# MonoPedal.net
KiCad netlist of a schematic drawn in EAGLE
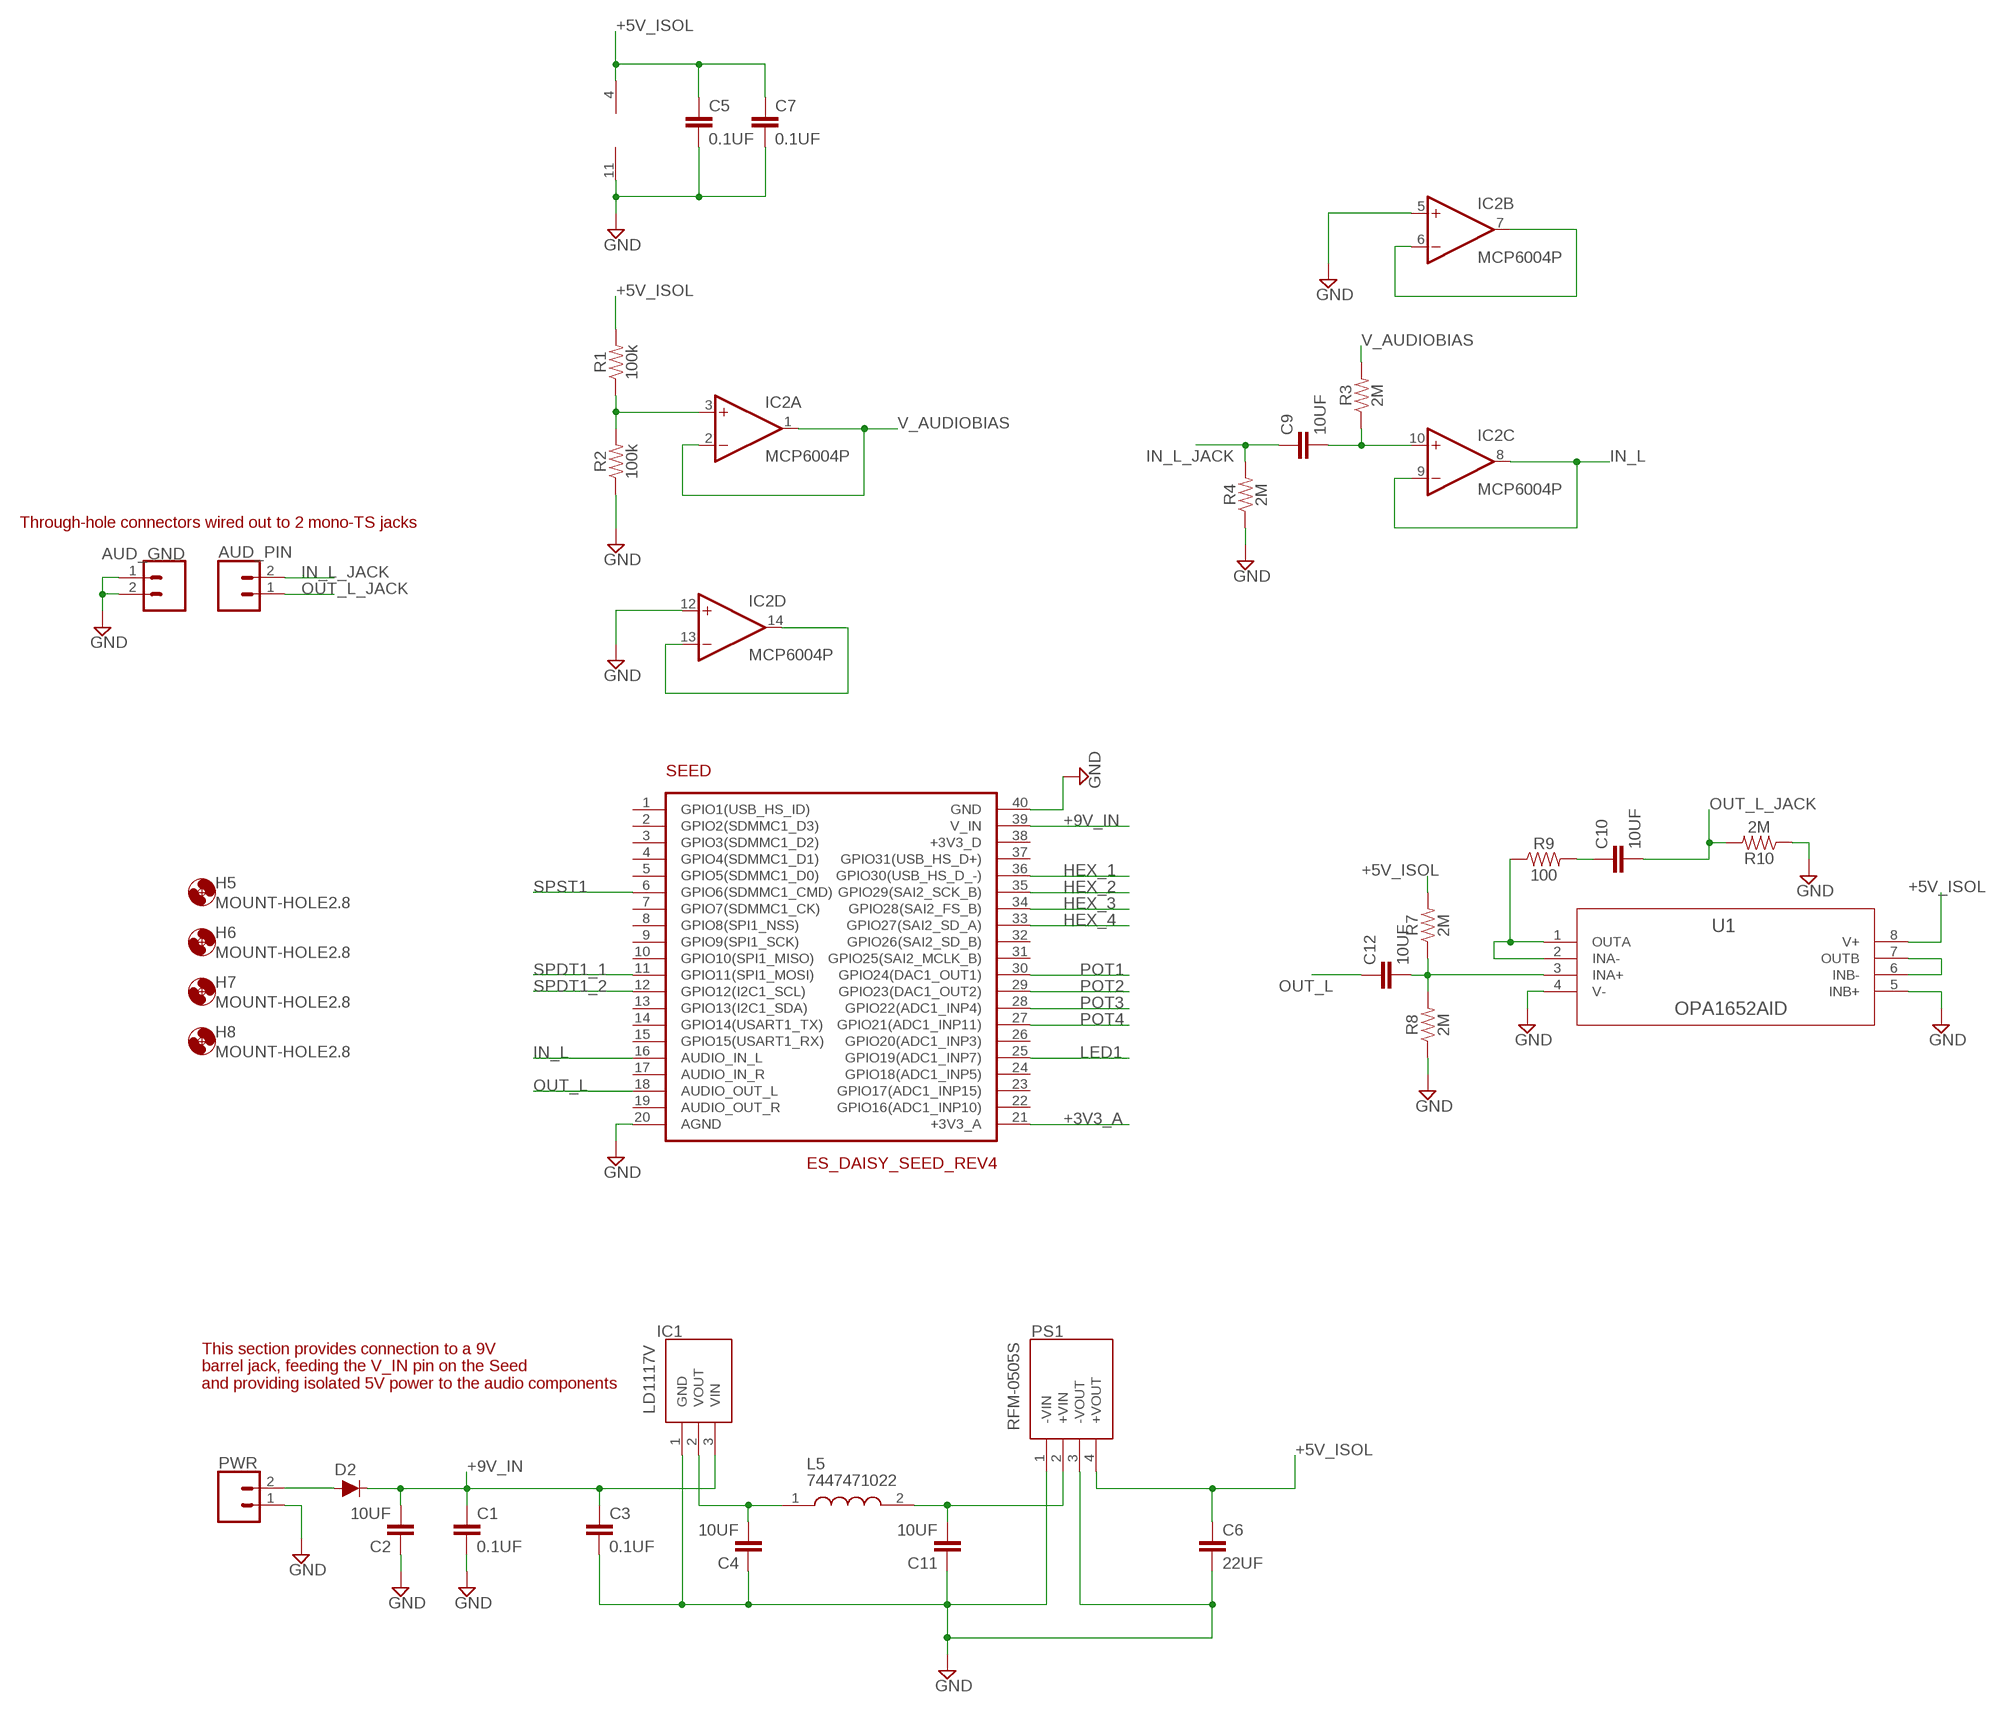
[diagram p0: schematic, sheet 1]
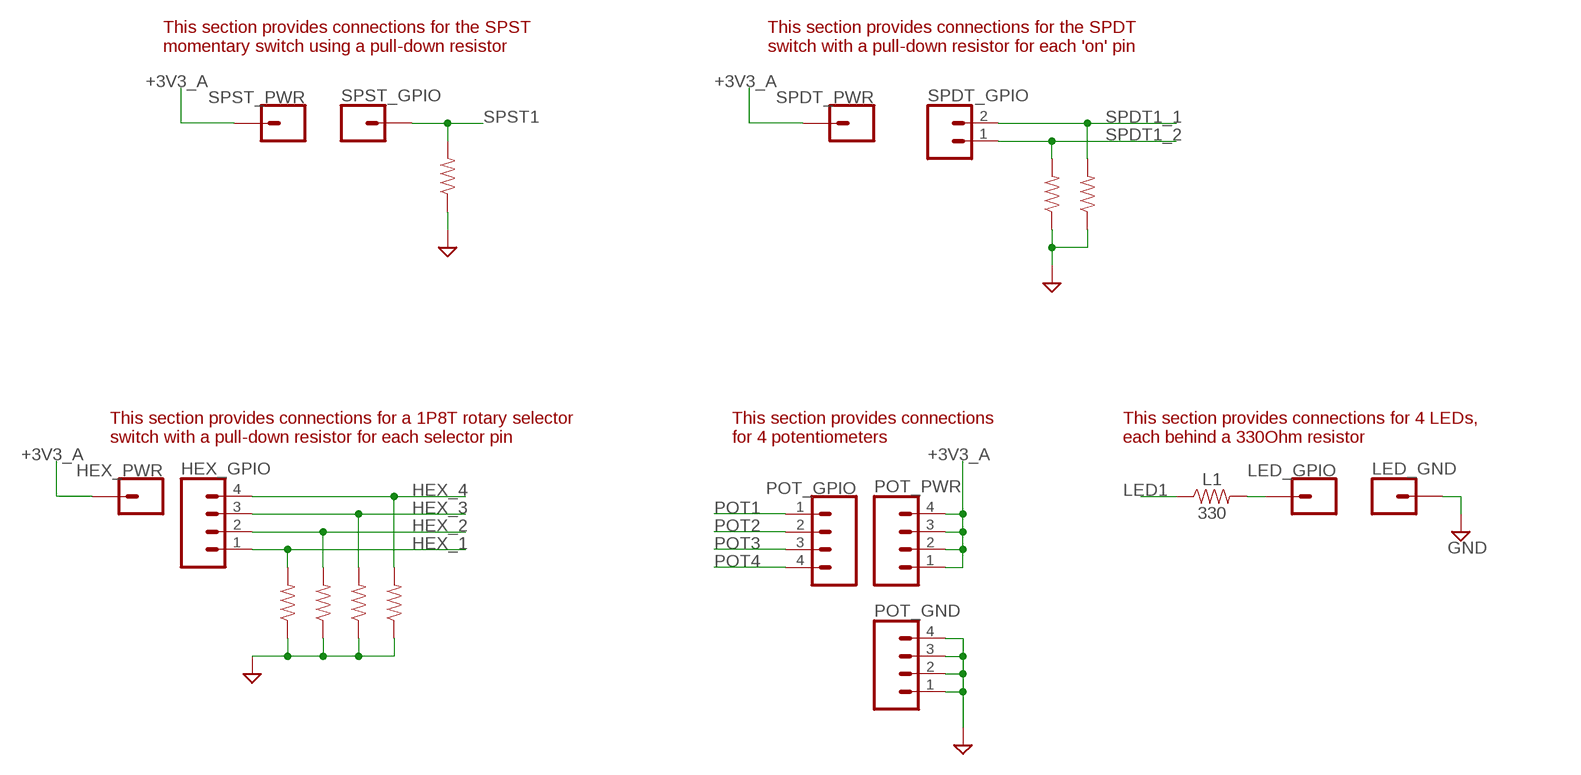
[diagram p1: schematic, sheet 2]

(export (version "E")
  (design (tool "Eeschema 10.0.6"))
  (components
    (comp (ref "AUD_GND")
      (value "CONN_02")
      (footprint "eagle-import:1X02")
      (libsource (lib "eagle-import") (part "CONN_02"))
    )
    (comp (ref "AUD_PIN")
      (value "CONN_02")
      (footprint "eagle-import:1X02")
      (libsource (lib "eagle-import") (part "CONN_02"))
    )
    (comp (ref "C1")
      (value "0.1UF")
      (footprint "eagle-import:CAP-PTH-SMALL-KIT")
      (libsource (lib "eagle-import") (part "0.1UF"))
    )
    (comp (ref "C2")
      (value "10UF")
      (footprint "eagle-import:CAP-PTH-SMALL-KIT")
      (libsource (lib "eagle-import") (part "10UF"))
    )
    (comp (ref "C3")
      (value "0.1UF")
      (footprint "eagle-import:CAP-PTH-SMALL-KIT")
      (libsource (lib "eagle-import") (part "0.1UF"))
    )
    (comp (ref "C4")
      (value "10UF")
      (footprint "eagle-import:CAP-PTH-SMALL-KIT")
      (libsource (lib "eagle-import") (part "10UF"))
    )
    (comp (ref "C5")
      (value "0.1UF")
      (footprint "eagle-import:CAP-PTH-SMALL-KIT")
      (libsource (lib "eagle-import") (part "0.1UF"))
    )
    (comp (ref "C6")
      (value "22UF")
      (footprint "eagle-import:CAP-PTH-SMALL-KIT")
      (libsource (lib "eagle-import") (part "22UF"))
    )
    (comp (ref "C7")
      (value "0.1UF")
      (footprint "eagle-import:CAP-PTH-SMALL-KIT")
      (libsource (lib "eagle-import") (part "0.1UF"))
    )
    (comp (ref "C9")
      (value "10UF")
      (footprint "eagle-import:CAP-PTH-SMALL-KIT")
      (libsource (lib "eagle-import") (part "10UF"))
    )
    (comp (ref "C10")
      (value "10UF")
      (footprint "eagle-import:CAP-PTH-SMALL-KIT")
      (libsource (lib "eagle-import") (part "10UF"))
    )
    (comp (ref "C11")
      (value "10UF")
      (footprint "eagle-import:CAP-PTH-SMALL-KIT")
      (libsource (lib "eagle-import") (part "10UF"))
    )
    (comp (ref "C12")
      (value "10UF")
      (footprint "eagle-import:CAP-PTH-SMALL-KIT")
      (libsource (lib "eagle-import") (part "10UF"))
    )
    (comp (ref "D2")
      (value "200mA/100V/1V")
      (footprint "eagle-import:DIODE-1N4148")
      (libsource (lib "eagle-import") (part "DIODE-1N4148"))
    )
    (comp (ref "H5")
      (value "MOUNT-HOLE2.8")
      (footprint "eagle-import:2,8")
      (libsource (lib "eagle-import") (part "MOUNT-HOLE2.8"))
    )
    (comp (ref "H6")
      (value "MOUNT-HOLE2.8")
      (footprint "eagle-import:2,8")
      (libsource (lib "eagle-import") (part "MOUNT-HOLE2.8"))
    )
    (comp (ref "H7")
      (value "MOUNT-HOLE2.8")
      (footprint "eagle-import:2,8")
      (libsource (lib "eagle-import") (part "MOUNT-HOLE2.8"))
    )
    (comp (ref "H8")
      (value "MOUNT-HOLE2.8")
      (footprint "eagle-import:2,8")
      (libsource (lib "eagle-import") (part "MOUNT-HOLE2.8"))
    )
    (comp (ref "IC1")
      (value "LD1117V")
      (footprint "eagle-import:TO255P460X1020X2008-3P")
      (fields (field (name "MOUSER_PART_NUMBER") "511-LD1117V"))
      (libsource (lib "eagle-import") (part "LD1117V"))
    )
    (comp (ref "IC2")
      (value "MCP6004P")
      (footprint "eagle-import:DIL14")
      (libsource (lib "eagle-import") (part "MCP6004P"))
    )
    (comp (ref "L5")
      (value "7447471022")
      (footprint "eagle-import:WE-TIS_111190")
      (fields (field (name "MOUSER_PART_NUMBER") "710-7447471022"))
      (libsource (lib "eagle-import") (part "7447471022"))
    )
    (comp (ref "PS1")
      (value "RFM-0505S")
      (footprint "eagle-import:RFM0505S")
      (fields (field (name "MOUSER_PART_NUMBER") "919-RFM-0505S"))
      (libsource (lib "eagle-import") (part "RFM-0505S"))
    )
    (comp (ref "PWR")
      (value "CONN_02")
      (footprint "eagle-import:1X02")
      (libsource (lib "eagle-import") (part "CONN_02"))
    )
    (comp (ref "R1")
      (value "100k")
      (footprint "eagle-import:AXIAL-0.3")
      (libsource (lib "eagle-import") (part "100KOHM-HORIZ-1/4W-5%"))
    )
    (comp (ref "R2")
      (value "100k")
      (footprint "eagle-import:AXIAL-0.3")
      (libsource (lib "eagle-import") (part "100KOHM-HORIZ-1/4W-5%"))
    )
    (comp (ref "R3")
      (value "2M")
      (footprint "eagle-import:AXIAL-0.3")
      (libsource (lib "eagle-import") (part "2MOHM-HORIZ-1/4W-5%"))
    )
    (comp (ref "R4")
      (value "2M")
      (footprint "eagle-import:AXIAL-0.3")
      (libsource (lib "eagle-import") (part "2MOHM-HORIZ-1/4W-5%"))
    )
    (comp (ref "R7")
      (value "2M")
      (footprint "eagle-import:AXIAL-0.3")
      (libsource (lib "eagle-import") (part "2MOHM-HORIZ-1/4W-5%"))
    )
    (comp (ref "R8")
      (value "2M")
      (footprint "eagle-import:AXIAL-0.3")
      (libsource (lib "eagle-import") (part "2MOHM-HORIZ-1/4W-5%"))
    )
    (comp (ref "R9")
      (value "100")
      (footprint "eagle-import:AXIAL-0.3")
      (libsource (lib "eagle-import") (part "100OHM-HORIZ-1/4W-1%"))
    )
    (comp (ref "R10")
      (value "2M")
      (footprint "eagle-import:AXIAL-0.3")
      (libsource (lib "eagle-import") (part "2MOHM-HORIZ-1/4W-5%"))
    )
    (comp (ref "SEED")
      (value "ES_DAISY_SEED_REV4")
      (footprint "eagle-import:ES_DAISY_SEED")
      (libsource (lib "eagle-import") (part "ES_DAISY_SEED_REV4"))
    )
    (comp (ref "U1")
      (value "OPA1652AID")
      (footprint "eagle-import:D8")
      (fields
        (field (name "GENERIC_PART_NUMBER") "OPA1652")
        (field (name "MANUFACTURER") "Texas Instruments")
      )
      (libsource (lib "eagle-import") (part "OPA1652AID"))
    )
    (comp (ref "D11")
      (value "10k")
      (footprint "eagle-import:AXIAL-0.3")
      (libsource (lib "eagle-import") (part "10KOHM-HORIZ-1/4W-5%"))
    )
    (comp (ref "D12")
      (value "10k")
      (footprint "eagle-import:AXIAL-0.3")
      (libsource (lib "eagle-import") (part "10KOHM-HORIZ-1/4W-5%"))
    )
    (comp (ref "H1")
      (value "10k")
      (footprint "eagle-import:AXIAL-0.3")
      (libsource (lib "eagle-import") (part "10KOHM-HORIZ-1/4W-5%"))
    )
    (comp (ref "H2")
      (value "10k")
      (footprint "eagle-import:AXIAL-0.3")
      (libsource (lib "eagle-import") (part "10KOHM-HORIZ-1/4W-5%"))
    )
    (comp (ref "H3")
      (value "10k")
      (footprint "eagle-import:AXIAL-0.3")
      (libsource (lib "eagle-import") (part "10KOHM-HORIZ-1/4W-5%"))
    )
    (comp (ref "H4")
      (value "10k")
      (footprint "eagle-import:AXIAL-0.3")
      (libsource (lib "eagle-import") (part "10KOHM-HORIZ-1/4W-5%"))
    )
    (comp (ref "HEX_GPIO")
      (value "CONN_04")
      (footprint "eagle-import:1X04")
      (libsource (lib "eagle-import") (part "CONN_04"))
    )
    (comp (ref "HEX_PWR")
      (value "CONN_01")
      (footprint "eagle-import:1X01")
      (libsource (lib "eagle-import") (part "CONN_01"))
    )
    (comp (ref "L1")
      (value "330")
      (footprint "eagle-import:AXIAL-0.3")
      (libsource (lib "eagle-import") (part "330OHM-HORIZ-1/10W-5%"))
    )
    (comp (ref "LED_GND")
      (value "CONN_01")
      (footprint "eagle-import:1X01")
      (libsource (lib "eagle-import") (part "CONN_01"))
    )
    (comp (ref "LED_GPIO")
      (value "CONN_01")
      (footprint "eagle-import:1X01")
      (libsource (lib "eagle-import") (part "CONN_01"))
    )
    (comp (ref "POT_GND")
      (value "CONN_04")
      (footprint "eagle-import:1X04")
      (libsource (lib "eagle-import") (part "CONN_04"))
    )
    (comp (ref "POT_GPIO")
      (value "CONN_04")
      (footprint "eagle-import:1X04")
      (libsource (lib "eagle-import") (part "CONN_04"))
    )
    (comp (ref "POT_PWR")
      (value "CONN_04")
      (footprint "eagle-import:1X04")
      (libsource (lib "eagle-import") (part "CONN_04"))
    )
    (comp (ref "S1")
      (value "10k")
      (footprint "eagle-import:AXIAL-0.3")
      (libsource (lib "eagle-import") (part "10KOHM-HORIZ-1/4W-5%"))
    )
    (comp (ref "SPDT_GPIO")
      (value "CONN_02")
      (footprint "eagle-import:1X02")
      (libsource (lib "eagle-import") (part "CONN_02"))
    )
    (comp (ref "SPDT_PWR")
      (value "CONN_01")
      (footprint "eagle-import:1X01")
      (libsource (lib "eagle-import") (part "CONN_01"))
    )
    (comp (ref "SPST_GPIO")
      (value "CONN_01")
      (footprint "eagle-import:1X01")
      (libsource (lib "eagle-import") (part "CONN_01"))
    )
    (comp (ref "SPST_PWR")
      (value "CONN_01")
      (footprint "eagle-import:1X01")
      (libsource (lib "eagle-import") (part "CONN_01"))
    )
  )
  (nets
    (net (code "1") (name "+3V3_A") (class "Default")
      (node (ref "HEX_PWR") (pin "1") (pinfunction "1_1") (pintype "passive"))
      (node (ref "POT_PWR") (pin "1") (pinfunction "1_1") (pintype "passive"))
      (node (ref "POT_PWR") (pin "2") (pinfunction "2_2") (pintype "passive"))
      (node (ref "POT_PWR") (pin "3") (pinfunction "3_3") (pintype "passive"))
      (node (ref "POT_PWR") (pin "4") (pinfunction "4_4") (pintype "passive"))
      (node (ref "SEED") (pin "21") (pinfunction "+3V3_A_21") (pintype "bidirectional"))
      (node (ref "SPDT_PWR") (pin "1") (pinfunction "1_1") (pintype "passive"))
      (node (ref "SPST_PWR") (pin "1") (pinfunction "1_1") (pintype "passive"))
    )
    (net (code "2") (name "+5V_ISOL") (class "Default")
      (node (ref "C5") (pin "1") (pinfunction "1_1") (pintype "passive"))
      (node (ref "C6") (pin "1") (pinfunction "1_1") (pintype "passive"))
      (node (ref "C7") (pin "1") (pinfunction "1_1") (pintype "passive"))
      (node (ref "IC2") (pin "4") (pinfunction "V+_4") (pintype "power_in"))
      (node (ref "PS1") (pin "4") (pinfunction "+VOUT_4") (pintype "bidirectional"))
      (node (ref "R1") (pin "P$2") (pinfunction "2_P$2") (pintype "passive"))
      (node (ref "R7") (pin "P$2") (pinfunction "2_P$2") (pintype "passive"))
      (node (ref "U1") (pin "8") (pinfunction "V+_8") (pintype "power_in"))
    )
    (net (code "3") (name "+9V_IN") (class "Default")
      (node (ref "C1") (pin "1") (pinfunction "1_1") (pintype "passive"))
      (node (ref "C2") (pin "2") (pinfunction "2_2") (pintype "passive"))
      (node (ref "C3") (pin "1") (pinfunction "1_1") (pintype "passive"))
      (node (ref "D2") (pin "C") (pinfunction "C_C") (pintype "passive"))
      (node (ref "IC1") (pin "3") (pinfunction "VIN_3") (pintype "bidirectional"))
      (node (ref "SEED") (pin "39") (pinfunction "V_IN_39") (pintype "bidirectional"))
    )
    (net (code "4") (name "GND") (class "Default")
      (node (ref "AUD_GND") (pin "1") (pinfunction "1_1") (pintype "passive"))
      (node (ref "AUD_GND") (pin "2") (pinfunction "2_2") (pintype "passive"))
      (node (ref "C1") (pin "2") (pinfunction "2_2") (pintype "passive"))
      (node (ref "C11") (pin "1") (pinfunction "1_1") (pintype "passive"))
      (node (ref "C2") (pin "1") (pinfunction "1_1") (pintype "passive"))
      (node (ref "C3") (pin "2") (pinfunction "2_2") (pintype "passive"))
      (node (ref "C4") (pin "1") (pinfunction "1_1") (pintype "passive"))
      (node (ref "C5") (pin "2") (pinfunction "2_2") (pintype "passive"))
      (node (ref "C6") (pin "2") (pinfunction "2_2") (pintype "passive"))
      (node (ref "C7") (pin "2") (pinfunction "2_2") (pintype "passive"))
      (node (ref "D11") (pin "P$1") (pinfunction "1_P$1") (pintype "passive"))
      (node (ref "D12") (pin "P$1") (pinfunction "1_P$1") (pintype "passive"))
      (node (ref "H1") (pin "P$1") (pinfunction "1_P$1") (pintype "passive"))
      (node (ref "H2") (pin "P$1") (pinfunction "1_P$1") (pintype "passive"))
      (node (ref "H3") (pin "P$1") (pinfunction "1_P$1") (pintype "passive"))
      (node (ref "H4") (pin "P$1") (pinfunction "1_P$1") (pintype "passive"))
      (node (ref "IC1") (pin "1") (pinfunction "GND_1") (pintype "bidirectional"))
      (node (ref "IC2") (pin "11") (pinfunction "V-_11") (pintype "power_in"))
      (node (ref "IC2") (pin "12") (pinfunction "+IN_12") (pintype "input"))
      (node (ref "IC2") (pin "5") (pinfunction "+IN_5") (pintype "input"))
      (node (ref "LED_GND") (pin "1") (pinfunction "1_1") (pintype "passive"))
      (node (ref "POT_GND") (pin "1") (pinfunction "1_1") (pintype "passive"))
      (node (ref "POT_GND") (pin "2") (pinfunction "2_2") (pintype "passive"))
      (node (ref "POT_GND") (pin "3") (pinfunction "3_3") (pintype "passive"))
      (node (ref "POT_GND") (pin "4") (pinfunction "4_4") (pintype "passive"))
      (node (ref "PS1") (pin "1") (pinfunction "-VIN_1") (pintype "bidirectional"))
      (node (ref "PS1") (pin "3") (pinfunction "-VOUT_3") (pintype "bidirectional"))
      (node (ref "PWR") (pin "1") (pinfunction "1_1") (pintype "passive"))
      (node (ref "R10") (pin "P$1") (pinfunction "1_P$1") (pintype "passive"))
      (node (ref "R2") (pin "P$1") (pinfunction "1_P$1") (pintype "passive"))
      (node (ref "R4") (pin "P$1") (pinfunction "1_P$1") (pintype "passive"))
      (node (ref "R8") (pin "P$1") (pinfunction "1_P$1") (pintype "passive"))
      (node (ref "S1") (pin "P$1") (pinfunction "1_P$1") (pintype "passive"))
      (node (ref "SEED") (pin "20") (pinfunction "AGND_20") (pintype "bidirectional"))
      (node (ref "SEED") (pin "40") (pinfunction "GND_40") (pintype "bidirectional"))
      (node (ref "U1") (pin "4") (pinfunction "V-_4") (pintype "power_in"))
      (node (ref "U1") (pin "5") (pinfunction "INB+_5") (pintype "input"))
    )
    (net (code "5") (name "HEX_1") (class "Default")
      (node (ref "H1") (pin "P$2") (pinfunction "2_P$2") (pintype "passive"))
      (node (ref "HEX_GPIO") (pin "1") (pinfunction "1_1") (pintype "passive"))
      (node (ref "SEED") (pin "36") (pinfunction "GPIO30(USB_HS_D_-)_36") (pintype "bidirectional"))
    )
    (net (code "6") (name "HEX_2") (class "Default")
      (node (ref "H2") (pin "P$2") (pinfunction "2_P$2") (pintype "passive"))
      (node (ref "HEX_GPIO") (pin "2") (pinfunction "2_2") (pintype "passive"))
      (node (ref "SEED") (pin "35") (pinfunction "GPIO29(SAI2_SCK_B)_35") (pintype "bidirectional"))
    )
    (net (code "7") (name "HEX_3") (class "Default")
      (node (ref "H3") (pin "P$2") (pinfunction "2_P$2") (pintype "passive"))
      (node (ref "HEX_GPIO") (pin "3") (pinfunction "3_3") (pintype "passive"))
      (node (ref "SEED") (pin "34") (pinfunction "GPIO28(SAI2_FS_B)_34") (pintype "bidirectional"))
    )
    (net (code "8") (name "HEX_4") (class "Default")
      (node (ref "H4") (pin "P$2") (pinfunction "2_P$2") (pintype "passive"))
      (node (ref "HEX_GPIO") (pin "4") (pinfunction "4_4") (pintype "passive"))
      (node (ref "SEED") (pin "33") (pinfunction "GPIO27(SAI2_SD_A)_33") (pintype "bidirectional"))
    )
    (net (code "9") (name "IN_L") (class "Default")
      (node (ref "IC2") (pin "8") (pinfunction "OUT_8") (pintype "output"))
      (node (ref "IC2") (pin "9") (pinfunction "-IN_9") (pintype "input"))
      (node (ref "SEED") (pin "16") (pinfunction "AUDIO_IN_L_16") (pintype "bidirectional"))
    )
    (net (code "10") (name "IN_L_JACK") (class "Default")
      (node (ref "AUD_PIN") (pin "2") (pinfunction "2_2") (pintype "passive"))
      (node (ref "C9") (pin "1") (pinfunction "1_1") (pintype "passive"))
      (node (ref "R4") (pin "P$2") (pinfunction "2_P$2") (pintype "passive"))
    )
    (net (code "11") (name "LED1") (class "Default")
      (node (ref "L1") (pin "P$1") (pinfunction "1_P$1") (pintype "passive"))
      (node (ref "SEED") (pin "25") (pinfunction "GPIO19(ADC1_INP7)_25") (pintype "bidirectional"))
    )
    (net (code "12") (name "Net-(D2-PadA)") (class "Default")
      (node (ref "D2") (pin "A") (pinfunction "A_A") (pintype "passive"))
      (node (ref "PWR") (pin "2") (pinfunction "2_2") (pintype "passive"))
    )
    (net (code "13") (name "Net-(IC1-VOUT)") (class "Default")
      (node (ref "C4") (pin "2") (pinfunction "2_2") (pintype "passive"))
      (node (ref "IC1") (pin "2") (pinfunction "VOUT_2") (pintype "bidirectional"))
      (node (ref "L5") (pin "1") (pinfunction "1_1") (pintype "bidirectional"))
    )
    (net (code "14") (name "Net-(IC2A-+IN)") (class "Default")
      (node (ref "IC2") (pin "3") (pinfunction "+IN_3") (pintype "input"))
      (node (ref "R1") (pin "P$1") (pinfunction "1_P$1") (pintype "passive"))
      (node (ref "R2") (pin "P$2") (pinfunction "2_P$2") (pintype "passive"))
    )
    (net (code "15") (name "Net-(IC2B--IN)") (class "Default")
      (node (ref "IC2") (pin "6") (pinfunction "-IN_6") (pintype "input"))
      (node (ref "IC2") (pin "7") (pinfunction "OUT_7") (pintype "output"))
    )
    (net (code "16") (name "Net-(IC2C-+IN)") (class "Default")
      (node (ref "C9") (pin "2") (pinfunction "2_2") (pintype "passive"))
      (node (ref "IC2") (pin "10") (pinfunction "+IN_10") (pintype "input"))
      (node (ref "R3") (pin "P$1") (pinfunction "1_P$1") (pintype "passive"))
    )
    (net (code "17") (name "Net-(IC2D--IN)") (class "Default")
      (node (ref "IC2") (pin "13") (pinfunction "-IN_13") (pintype "input"))
      (node (ref "IC2") (pin "14") (pinfunction "OUT_14") (pintype "output"))
    )
    (net (code "18") (name "Net-(L1-2)") (class "Default")
      (node (ref "L1") (pin "P$2") (pinfunction "2_P$2") (pintype "passive"))
      (node (ref "LED_GPIO") (pin "1") (pinfunction "1_1") (pintype "passive"))
    )
    (net (code "19") (name "Net-(PS1-+VIN)") (class "Default")
      (node (ref "C11") (pin "2") (pinfunction "2_2") (pintype "passive"))
      (node (ref "L5") (pin "2") (pinfunction "2_2") (pintype "bidirectional"))
      (node (ref "PS1") (pin "2") (pinfunction "+VIN_2") (pintype "bidirectional"))
    )
    (net (code "20") (name "Net-(R7-1)") (class "Default")
      (node (ref "C12") (pin "2") (pinfunction "2_2") (pintype "passive"))
      (node (ref "R7") (pin "P$1") (pinfunction "1_P$1") (pintype "passive"))
      (node (ref "R8") (pin "P$2") (pinfunction "2_P$2") (pintype "passive"))
      (node (ref "U1") (pin "3") (pinfunction "INA+_3") (pintype "input"))
    )
    (net (code "21") (name "Net-(R9-1)") (class "Default")
      (node (ref "R9") (pin "P$1") (pinfunction "1_P$1") (pintype "passive"))
      (node (ref "U1") (pin "1") (pinfunction "OUTA_1") (pintype "output"))
      (node (ref "U1") (pin "2") (pinfunction "INA-_2") (pintype "input"))
    )
    (net (code "22") (name "Net-(R9-2)") (class "Default")
      (node (ref "C10") (pin "1") (pinfunction "1_1") (pintype "passive"))
      (node (ref "R9") (pin "P$2") (pinfunction "2_P$2") (pintype "passive"))
    )
    (net (code "23") (name "Net-(U1-INB-)") (class "Default")
      (node (ref "U1") (pin "6") (pinfunction "INB-_6") (pintype "input"))
      (node (ref "U1") (pin "7") (pinfunction "OUTB_7") (pintype "output"))
    )
    (net (code "24") (name "OUT_L") (class "Default")
      (node (ref "C12") (pin "1") (pinfunction "1_1") (pintype "passive"))
      (node (ref "SEED") (pin "18") (pinfunction "AUDIO_OUT_L_18") (pintype "bidirectional"))
    )
    (net (code "25") (name "OUT_L_JACK") (class "Default")
      (node (ref "AUD_PIN") (pin "1") (pinfunction "1_1") (pintype "passive"))
      (node (ref "C10") (pin "2") (pinfunction "2_2") (pintype "passive"))
      (node (ref "R10") (pin "P$2") (pinfunction "2_P$2") (pintype "passive"))
    )
    (net (code "26") (name "POT1") (class "Default")
      (node (ref "POT_GPIO") (pin "1") (pinfunction "1_1") (pintype "passive"))
      (node (ref "SEED") (pin "30") (pinfunction "GPIO24(DAC1_OUT1)_30") (pintype "bidirectional"))
    )
    (net (code "27") (name "POT2") (class "Default")
      (node (ref "POT_GPIO") (pin "2") (pinfunction "2_2") (pintype "passive"))
      (node (ref "SEED") (pin "29") (pinfunction "GPIO23(DAC1_OUT2)_29") (pintype "bidirectional"))
    )
    (net (code "28") (name "POT3") (class "Default")
      (node (ref "POT_GPIO") (pin "3") (pinfunction "3_3") (pintype "passive"))
      (node (ref "SEED") (pin "28") (pinfunction "GPIO22(ADC1_INP4)_28") (pintype "bidirectional"))
    )
    (net (code "29") (name "POT4") (class "Default")
      (node (ref "POT_GPIO") (pin "4") (pinfunction "4_4") (pintype "passive"))
      (node (ref "SEED") (pin "27") (pinfunction "GPIO21(ADC1_INP11)_27") (pintype "bidirectional"))
    )
    (net (code "30") (name "SPDT1_1") (class "Default")
      (node (ref "D11") (pin "P$2") (pinfunction "2_P$2") (pintype "passive"))
      (node (ref "SEED") (pin "11") (pinfunction "GPIO11(SPI1_MOSI)_11") (pintype "bidirectional"))
      (node (ref "SPDT_GPIO") (pin "2") (pinfunction "2_2") (pintype "passive"))
    )
    (net (code "31") (name "SPDT1_2") (class "Default")
      (node (ref "D12") (pin "P$2") (pinfunction "2_P$2") (pintype "passive"))
      (node (ref "SEED") (pin "12") (pinfunction "GPIO12(I2C1_SCL)_12") (pintype "bidirectional"))
      (node (ref "SPDT_GPIO") (pin "1") (pinfunction "1_1") (pintype "passive"))
    )
    (net (code "32") (name "SPST1") (class "Default")
      (node (ref "S1") (pin "P$2") (pinfunction "2_P$2") (pintype "passive"))
      (node (ref "SEED") (pin "6") (pinfunction "GPIO6(SDMMC1_CMD)_6") (pintype "bidirectional"))
      (node (ref "SPST_GPIO") (pin "1") (pinfunction "1_1") (pintype "passive"))
    )
    (net (code "33") (name "V_AUDIOBIAS") (class "Default")
      (node (ref "IC2") (pin "1") (pinfunction "OUT_1") (pintype "output"))
      (node (ref "IC2") (pin "2") (pinfunction "-IN_2") (pintype "input"))
      (node (ref "R3") (pin "P$2") (pinfunction "2_P$2") (pintype "passive"))
    )
    (net (code "34") (name "unconnected-(SEED-+3V3_D-Pad38)") (class "Default")
      (node (ref "SEED") (pin "38") (pinfunction "+3V3_D_38") (pintype "bidirectional"))
    )
    (net (code "35") (name "unconnected-(SEED-AUDIO_IN_R-Pad17)") (class "Default")
      (node (ref "SEED") (pin "17") (pinfunction "AUDIO_IN_R_17") (pintype "bidirectional"))
    )
    (net (code "36") (name "unconnected-(SEED-AUDIO_OUT_R-Pad19)") (class "Default")
      (node (ref "SEED") (pin "19") (pinfunction "AUDIO_OUT_R_19") (pintype "bidirectional"))
    )
    (net (code "37") (name "unconnected-(SEED-GPIO1(USB_HS_ID)-Pad1)") (class "Default")
      (node (ref "SEED") (pin "1") (pinfunction "GPIO1(USB_HS_ID)_1") (pintype "bidirectional"))
    )
    (net (code "38") (name "unconnected-(SEED-GPIO2(SDMMC1_D3)-Pad2)") (class "Default")
      (node (ref "SEED") (pin "2") (pinfunction "GPIO2(SDMMC1_D3)_2") (pintype "bidirectional"))
    )
    (net (code "39") (name "unconnected-(SEED-GPIO3(SDMMC1_D2)-Pad3)") (class "Default")
      (node (ref "SEED") (pin "3") (pinfunction "GPIO3(SDMMC1_D2)_3") (pintype "bidirectional"))
    )
    (net (code "40") (name "unconnected-(SEED-GPIO4(SDMMC1_D1)-Pad4)") (class "Default")
      (node (ref "SEED") (pin "4") (pinfunction "GPIO4(SDMMC1_D1)_4") (pintype "bidirectional"))
    )
    (net (code "41") (name "unconnected-(SEED-GPIO5(SDMMC1_D0)-Pad5)") (class "Default")
      (node (ref "SEED") (pin "5") (pinfunction "GPIO5(SDMMC1_D0)_5") (pintype "bidirectional"))
    )
    (net (code "42") (name "unconnected-(SEED-GPIO7(SDMMC1_CK)-Pad7)") (class "Default")
      (node (ref "SEED") (pin "7") (pinfunction "GPIO7(SDMMC1_CK)_7") (pintype "bidirectional"))
    )
    (net (code "43") (name "unconnected-(SEED-GPIO8(SPI1_NSS)-Pad8)") (class "Default")
      (node (ref "SEED") (pin "8") (pinfunction "GPIO8(SPI1_NSS)_8") (pintype "bidirectional"))
    )
    (net (code "44") (name "unconnected-(SEED-GPIO9(SPI1_SCK)-Pad9)") (class "Default")
      (node (ref "SEED") (pin "9") (pinfunction "GPIO9(SPI1_SCK)_9") (pintype "bidirectional"))
    )
    (net (code "45") (name "unconnected-(SEED-GPIO10(SPI1_MISO)-Pad10)") (class "Default")
      (node (ref "SEED") (pin "10") (pinfunction "GPIO10(SPI1_MISO)_10") (pintype "bidirectional"))
    )
    (net (code "46") (name "unconnected-(SEED-GPIO13(I2C1_SDA)-Pad13)") (class "Default")
      (node (ref "SEED") (pin "13") (pinfunction "GPIO13(I2C1_SDA)_13") (pintype "bidirectional"))
    )
    (net (code "47") (name "unconnected-(SEED-GPIO14(USART1_TX)-Pad14)") (class "Default")
      (node (ref "SEED") (pin "14") (pinfunction "GPIO14(USART1_TX)_14") (pintype "bidirectional"))
    )
    (net (code "48") (name "unconnected-(SEED-GPIO15(USART1_RX)-Pad15)") (class "Default")
      (node (ref "SEED") (pin "15") (pinfunction "GPIO15(USART1_RX)_15") (pintype "bidirectional"))
    )
    (net (code "49") (name "unconnected-(SEED-GPIO16(ADC1_INP10)-Pad22)") (class "Default")
      (node (ref "SEED") (pin "22") (pinfunction "GPIO16(ADC1_INP10)_22") (pintype "bidirectional"))
    )
    (net (code "50") (name "unconnected-(SEED-GPIO17(ADC1_INP15)-Pad23)") (class "Default")
      (node (ref "SEED") (pin "23") (pinfunction "GPIO17(ADC1_INP15)_23") (pintype "bidirectional"))
    )
    (net (code "51") (name "unconnected-(SEED-GPIO18(ADC1_INP5)-Pad24)") (class "Default")
      (node (ref "SEED") (pin "24") (pinfunction "GPIO18(ADC1_INP5)_24") (pintype "bidirectional"))
    )
    (net (code "52") (name "unconnected-(SEED-GPIO20(ADC1_INP3)-Pad26)") (class "Default")
      (node (ref "SEED") (pin "26") (pinfunction "GPIO20(ADC1_INP3)_26") (pintype "bidirectional"))
    )
    (net (code "53") (name "unconnected-(SEED-GPIO25(SAI2_MCLK_B)-Pad31)") (class "Default")
      (node (ref "SEED") (pin "31") (pinfunction "GPIO25(SAI2_MCLK_B)_31") (pintype "bidirectional"))
    )
    (net (code "54") (name "unconnected-(SEED-GPIO26(SAI2_SD_B)-Pad32)") (class "Default")
      (node (ref "SEED") (pin "32") (pinfunction "GPIO26(SAI2_SD_B)_32") (pintype "bidirectional"))
    )
    (net (code "55") (name "unconnected-(SEED-GPIO31(USB_HS_D+)-Pad37)") (class "Default")
      (node (ref "SEED") (pin "37") (pinfunction "GPIO31(USB_HS_D+)_37") (pintype "bidirectional"))
    )
  )
)
